# DelayPCB.net
KiCad netlist of a schematic drawn in EasyEDA
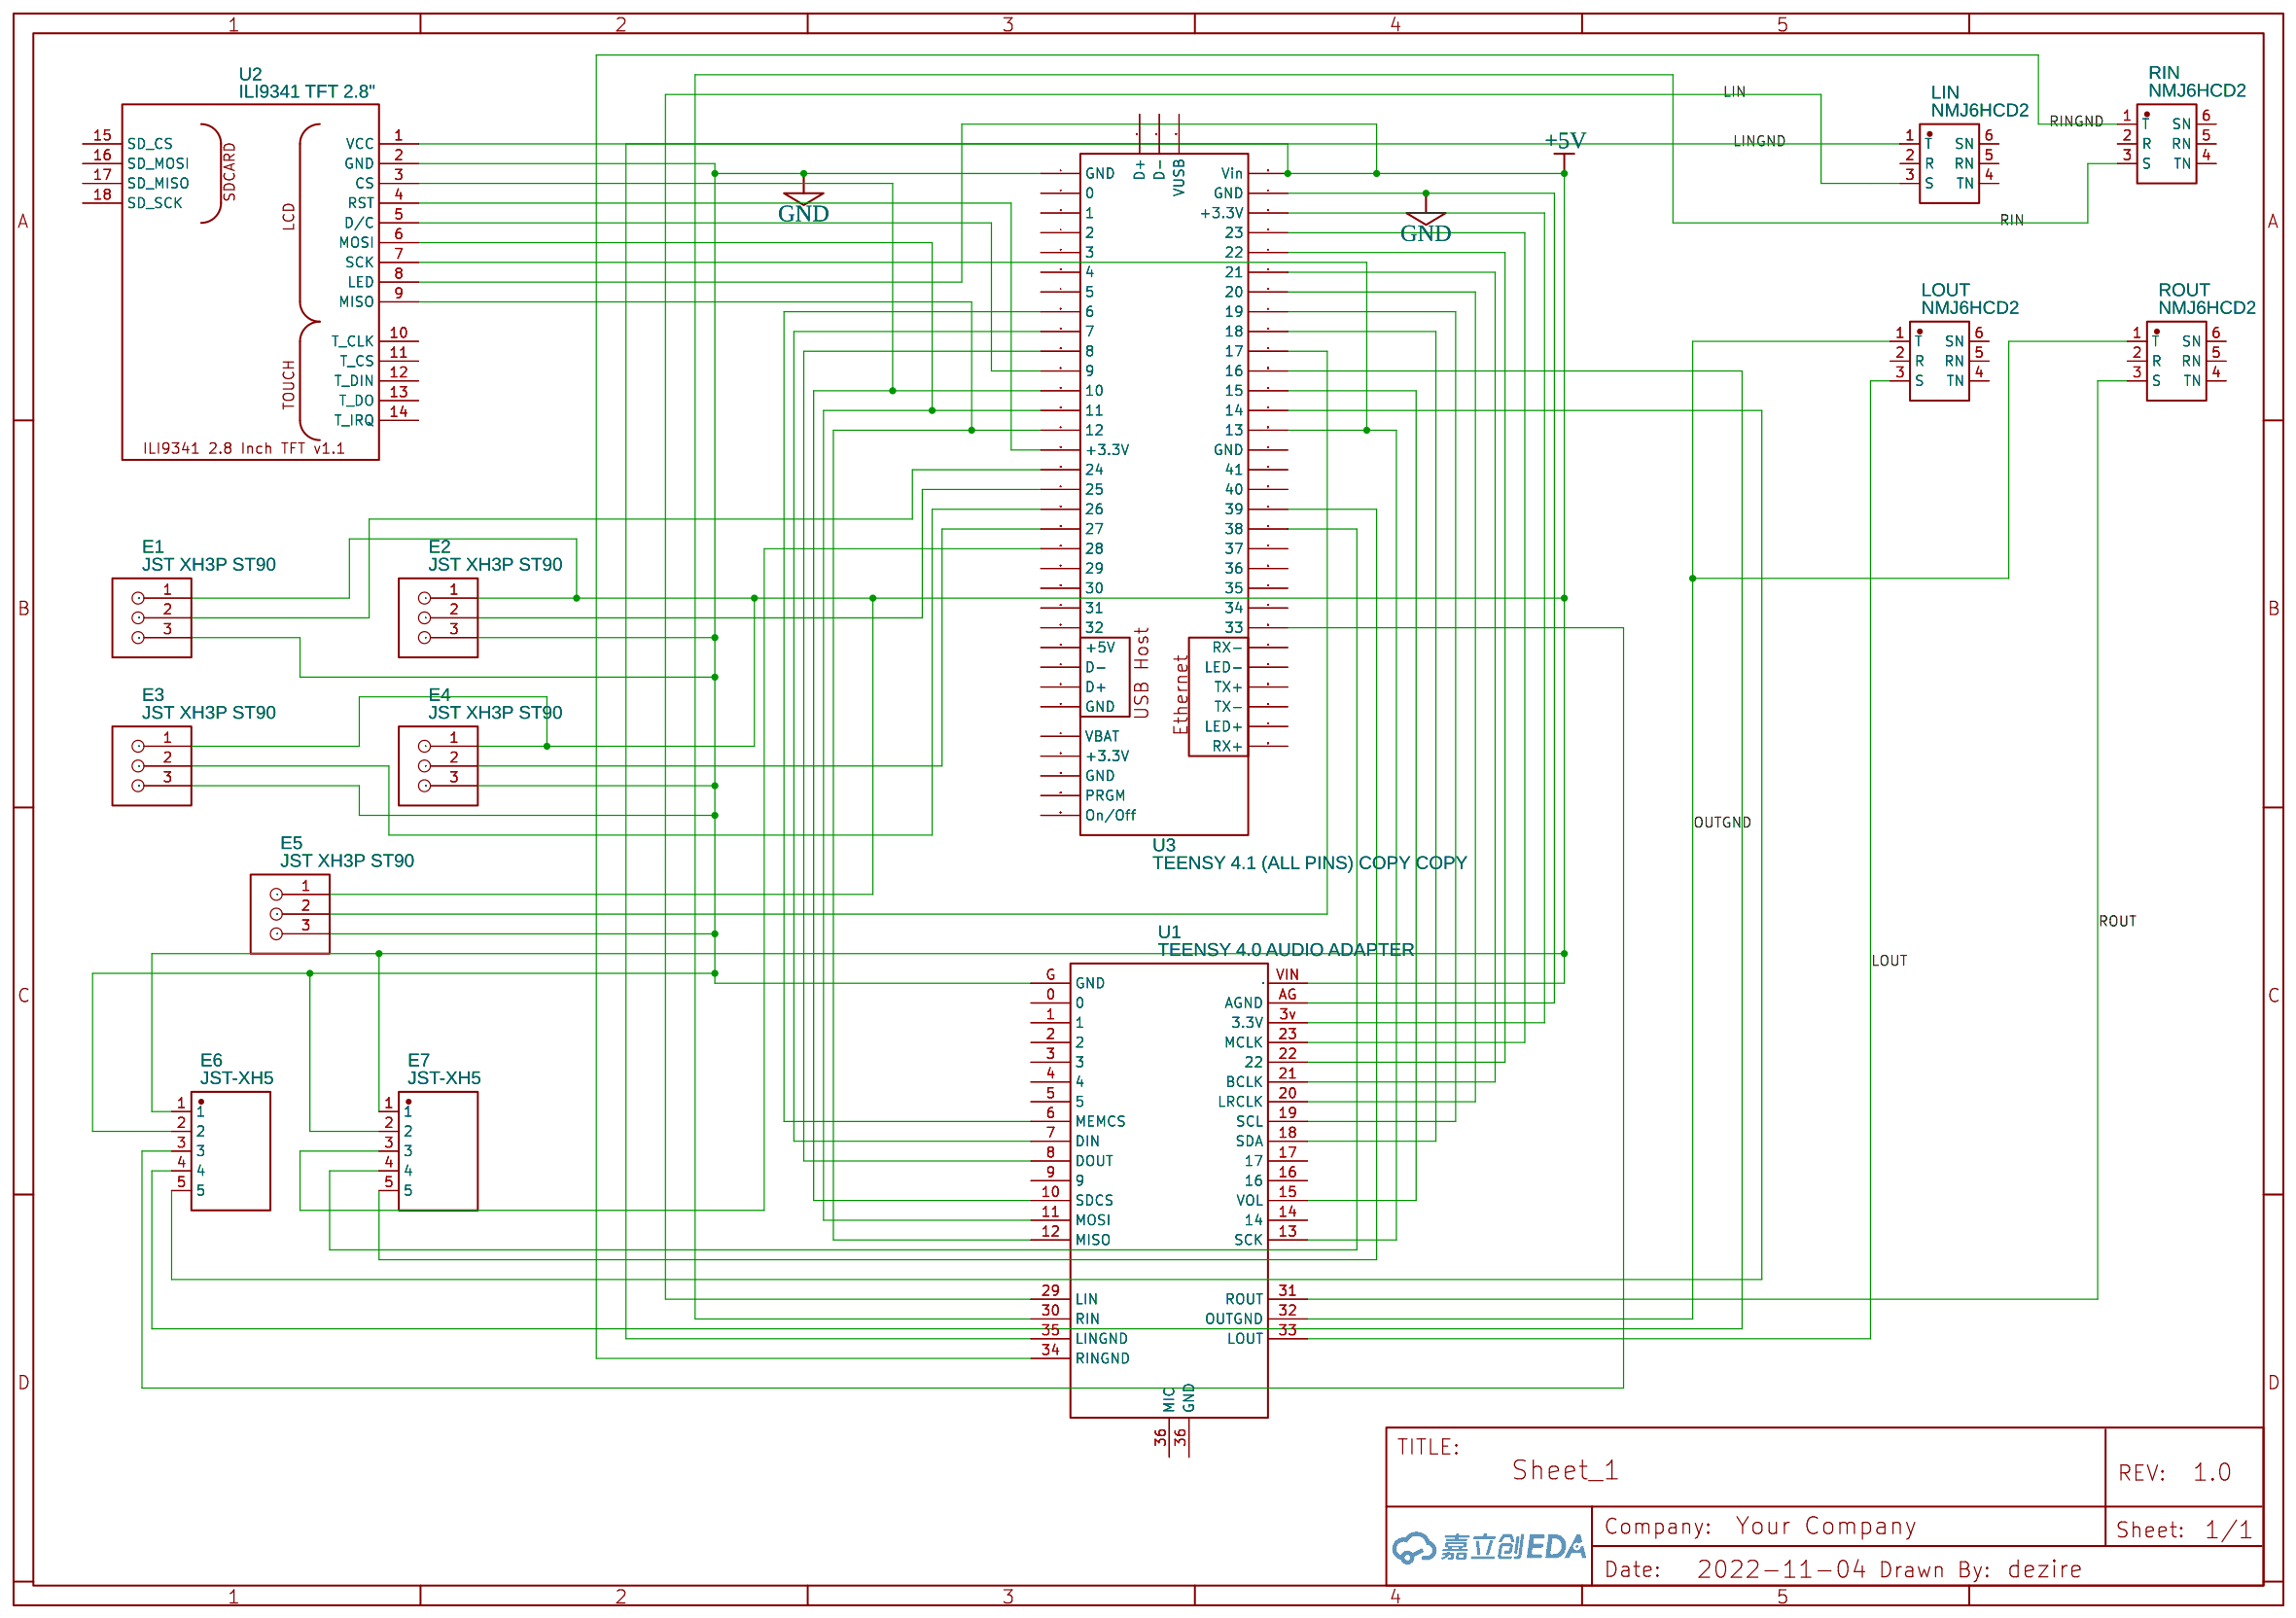
[diagram p0: schematic sheet]

(export (version "E")
  (design (tool "Eeschema 10.0.6"))
  (components
    (comp (ref "E1") (value "JST XH3P ST90") (libsource (lib "") (part "JST XH3P ST90")))
    (comp (ref "E2") (value "JST XH3P ST90") (libsource (lib "") (part "JST XH3P ST90")))
    (comp (ref "E3") (value "JST XH3P ST90") (libsource (lib "") (part "JST XH3P ST90")))
    (comp (ref "E4") (value "JST XH3P ST90") (libsource (lib "") (part "JST XH3P ST90")))
    (comp (ref "E5") (value "JST XH3P ST90") (libsource (lib "") (part "JST XH3P ST90")))
    (comp (ref "E6")
      (value "JST-XH5")
      (fields (field (name "BOM_Supplier Part") "JST XH5P ST"))
      (libsource (lib "") (part "JST-XH5"))
    )
    (comp (ref "E7")
      (value "JST-XH5")
      (fields (field (name "BOM_Supplier Part") "JST XH5P ST"))
      (libsource (lib "") (part "JST-XH5"))
    )
    (comp (ref "LIN")
      (value "NMJ6HCD2")
      (fields (field (name "BOM_Supplier Part") "C368502"))
      (libsource (lib "") (part "NMJ6HCD2_2"))
    )
    (comp (ref "LOUT")
      (value "NMJ6HCD2")
      (fields (field (name "BOM_Supplier Part") "C368502"))
      (libsource (lib "") (part "NMJ6HCD2_3"))
    )
    (comp (ref "RIN")
      (value "NMJ6HCD2")
      (fields (field (name "BOM_Supplier Part") "C368502"))
      (libsource (lib "") (part "NMJ6HCD2_1"))
    )
    (comp (ref "ROUT")
      (value "NMJ6HCD2")
      (fields (field (name "BOM_Supplier Part") "C368502"))
      (libsource (lib "") (part "NMJ6HCD2"))
    )
    (comp (ref "U1")
      (value "TEENSY 4.0 AUDIO ADAPTER")
      (fields (field (name "BOM_Manufacturer Part") "New SchematicLib"))
      (libsource (lib "") (part "TEENSY 4.0 AUDIO ADAPTER"))
    )
    (comp (ref "U2") (value "ILI9341 TFT 2.8\"") (libsource (lib "") (part "ILI9341 TFT 2.8{dblquote}")))
    (comp (ref "U3")
      (value "TEENSY 4.1 (ALL PINS) COPY COPY")
      (libsource (lib "") (part "TEENSY 4.1 (ALL PINS) COPY COPY"))
    )
  )
  (nets
    (net (code "1") (name "+5V") (class "Default")
      (node (ref "E1") (pin "1") (pinfunction "1_1") (pintype "bidirectional"))
      (node (ref "E2") (pin "1") (pinfunction "1_1") (pintype "bidirectional"))
      (node (ref "E3") (pin "1") (pinfunction "1_1") (pintype "bidirectional"))
      (node (ref "E4") (pin "1") (pinfunction "1_1") (pintype "bidirectional"))
      (node (ref "E5") (pin "1") (pinfunction "1_1") (pintype "bidirectional"))
      (node (ref "E6") (pin "1") (pinfunction "1_1") (pintype "unspecified"))
      (node (ref "E7") (pin "1") (pinfunction "1_1") (pintype "unspecified"))
      (node (ref "U1") (pin "VIN") (pinfunction "28_VIN") (pintype "unspecified"))
      (node (ref "U2") (pin "1") (pinfunction "VCC_1") (pintype "unspecified"))
      (node (ref "U2") (pin "8") (pinfunction "LED_8") (pintype "unspecified"))
      (node (ref "U3") (pin "48") (pinfunction "Vin_48") (pintype "unspecified"))
    )
    (net (code "2") (name "/LIN") (class "Default")
      (node (ref "LIN") (pin "3") (pinfunction "S_3") (pintype "unspecified"))
      (node (ref "U1") (pin "29") (pinfunction "LIN_29") (pintype "unspecified"))
    )
    (net (code "3") (name "/LINGND") (class "Default")
      (node (ref "LIN") (pin "1") (pinfunction "T_1") (pintype "unspecified"))
      (node (ref "U1") (pin "35") (pinfunction "LINGND_35") (pintype "unspecified"))
    )
    (net (code "4") (name "/LOUT") (class "Default")
      (node (ref "LOUT") (pin "3") (pinfunction "S_3") (pintype "unspecified"))
      (node (ref "U1") (pin "33") (pinfunction "LOUT_33") (pintype "unspecified"))
    )
    (net (code "5") (name "/OUTGND") (class "Default")
      (node (ref "LOUT") (pin "1") (pinfunction "T_1") (pintype "unspecified"))
      (node (ref "ROUT") (pin "1") (pinfunction "T_1") (pintype "unspecified"))
      (node (ref "U1") (pin "32") (pinfunction "OUTGND_32") (pintype "unspecified"))
    )
    (net (code "6") (name "/RIN") (class "Default")
      (node (ref "RIN") (pin "3") (pinfunction "S_3") (pintype "unspecified"))
      (node (ref "U1") (pin "30") (pinfunction "RIN_30") (pintype "unspecified"))
    )
    (net (code "7") (name "/RINGND") (class "Default")
      (node (ref "RIN") (pin "1") (pinfunction "T_1") (pintype "unspecified"))
      (node (ref "U1") (pin "34") (pinfunction "RINGND_34") (pintype "unspecified"))
    )
    (net (code "8") (name "/ROUT") (class "Default")
      (node (ref "ROUT") (pin "3") (pinfunction "S_3") (pintype "unspecified"))
      (node (ref "U1") (pin "31") (pinfunction "ROUT_31") (pintype "unspecified"))
    )
    (net (code "9") (name "GND") (class "Default")
      (node (ref "E1") (pin "3") (pinfunction "3_3") (pintype "bidirectional"))
      (node (ref "E2") (pin "3") (pinfunction "3_3") (pintype "bidirectional"))
      (node (ref "E3") (pin "3") (pinfunction "3_3") (pintype "bidirectional"))
      (node (ref "E4") (pin "3") (pinfunction "3_3") (pintype "bidirectional"))
      (node (ref "E5") (pin "3") (pinfunction "3_3") (pintype "bidirectional"))
      (node (ref "E6") (pin "2") (pinfunction "2_2") (pintype "unspecified"))
      (node (ref "E7") (pin "2") (pinfunction "2_2") (pintype "unspecified"))
      (node (ref "U1") (pin "AG") (pinfunction "AGND_AG") (pintype "unspecified"))
      (node (ref "U1") (pin "G") (pinfunction "GND_G") (pintype "unspecified"))
      (node (ref "U2") (pin "2") (pinfunction "GND_2") (pintype "unspecified"))
      (node (ref "U3") (pin "1") (pinfunction "GND_1") (pintype "unspecified"))
      (node (ref "U3") (pin "47") (pinfunction "GND_47") (pintype "unspecified"))
    )
    (net (code "10") (name "Net-(U1-3.3V)") (class "Default")
      (node (ref "U1") (pin "3v") (pinfunction "3.3V_3v") (pintype "unspecified"))
      (node (ref "U3") (pin "46") (pinfunction "+3.3V_46") (pintype "unspecified"))
    )
    (net (code "11") (name "Net-(U1-BCLK)") (class "Default")
      (node (ref "U1") (pin "21") (pinfunction "BCLK_21") (pintype "unspecified"))
      (node (ref "U3") (pin "43") (pinfunction "21_43") (pintype "unspecified"))
    )
    (net (code "12") (name "Net-(U1-DIN)") (class "Default")
      (node (ref "U1") (pin "7") (pinfunction "DIN_7") (pintype "unspecified"))
      (node (ref "U3") (pin "9") (pinfunction "7_9") (pintype "unspecified"))
    )
    (net (code "13") (name "Net-(U1-DOUT)") (class "Default")
      (node (ref "U1") (pin "8") (pinfunction "DOUT_8") (pintype "unspecified"))
      (node (ref "U3") (pin "10") (pinfunction "8_10") (pintype "unspecified"))
    )
    (net (code "14") (name "Net-(U1-LRCLK)") (class "Default")
      (node (ref "U1") (pin "20") (pinfunction "LRCLK_20") (pintype "unspecified"))
      (node (ref "U3") (pin "42") (pinfunction "20_42") (pintype "unspecified"))
    )
    (net (code "15") (name "Net-(U1-MCLK)") (class "Default")
      (node (ref "U1") (pin "23") (pinfunction "MCLK_23") (pintype "unspecified"))
      (node (ref "U3") (pin "45") (pinfunction "23_45") (pintype "unspecified"))
    )
    (net (code "16") (name "Net-(U1-MEMCS)") (class "Default")
      (node (ref "U1") (pin "6") (pinfunction "MEMCS_6") (pintype "unspecified"))
      (node (ref "U3") (pin "8") (pinfunction "6_8") (pintype "unspecified"))
    )
    (net (code "17") (name "Net-(U1-MISO)") (class "Default")
      (node (ref "U1") (pin "12") (pinfunction "MISO_12") (pintype "unspecified"))
      (node (ref "U2") (pin "9") (pinfunction "MISO_9") (pintype "unspecified"))
      (node (ref "U3") (pin "14") (pinfunction "12_14") (pintype "unspecified"))
    )
    (net (code "18") (name "Net-(U1-MOSI)") (class "Default")
      (node (ref "U1") (pin "11") (pinfunction "MOSI_11") (pintype "unspecified"))
      (node (ref "U2") (pin "6") (pinfunction "MOSI_6") (pintype "unspecified"))
      (node (ref "U3") (pin "13") (pinfunction "11_13") (pintype "unspecified"))
    )
    (net (code "19") (name "Net-(U1-SCK)") (class "Default")
      (node (ref "U1") (pin "13") (pinfunction "SCK_13") (pintype "unspecified"))
      (node (ref "U2") (pin "7") (pinfunction "SCK_7") (pintype "unspecified"))
      (node (ref "U3") (pin "35") (pinfunction "13_35") (pintype "unspecified"))
    )
    (net (code "20") (name "Net-(U1-SCL)") (class "Default")
      (node (ref "U1") (pin "19") (pinfunction "SCL_19") (pintype "unspecified"))
      (node (ref "U3") (pin "41") (pinfunction "19_41") (pintype "unspecified"))
    )
    (net (code "21") (name "Net-(U1-SDA)") (class "Default")
      (node (ref "U1") (pin "18") (pinfunction "SDA_18") (pintype "unspecified"))
      (node (ref "U3") (pin "40") (pinfunction "18_40") (pintype "unspecified"))
    )
    (net (code "22") (name "Net-(U1-SDCS)") (class "Default")
      (node (ref "U1") (pin "10") (pinfunction "SDCS_10") (pintype "unspecified"))
      (node (ref "U2") (pin "3") (pinfunction "CS_3") (pintype "unspecified"))
      (node (ref "U3") (pin "12") (pinfunction "10_12") (pintype "unspecified"))
    )
    (net (code "23") (name "Net-(U1-VOL)") (class "Default")
      (node (ref "U1") (pin "15") (pinfunction "VOL_15") (pintype "unspecified"))
      (node (ref "U3") (pin "37") (pinfunction "15_37") (pintype "unspecified"))
    )
    (net (code "24") (name "Net-(U2-D{slash}C)") (class "Default")
      (node (ref "U2") (pin "5") (pinfunction "D/C_5") (pintype "unspecified"))
      (node (ref "U3") (pin "11") (pinfunction "9_11") (pintype "unspecified"))
    )
    (net (code "25") (name "Net-(U2-RST)") (class "Default")
      (node (ref "U2") (pin "4") (pinfunction "RST_4") (pintype "unspecified"))
      (node (ref "U3") (pin "15") (pinfunction "+3.3V_15") (pintype "unspecified"))
    )
    (net (code "26") (name "Net-(U3-14)") (class "Default")
      (node (ref "E6") (pin "5") (pinfunction "5_5") (pintype "unspecified"))
      (node (ref "U3") (pin "36") (pinfunction "14_36") (pintype "unspecified"))
    )
    (net (code "27") (name "Net-(U3-16)") (class "Default")
      (node (ref "E6") (pin "4") (pinfunction "4_4") (pintype "unspecified"))
      (node (ref "U3") (pin "38") (pinfunction "16_38") (pintype "unspecified"))
    )
    (net (code "28") (name "Net-(U3-17)") (class "Default")
      (node (ref "E5") (pin "2") (pinfunction "2_2") (pintype "bidirectional"))
      (node (ref "U3") (pin "39") (pinfunction "17_39") (pintype "unspecified"))
    )
    (net (code "29") (name "Net-(U3-22)") (class "Default")
      (node (ref "U1") (pin "22") (pinfunction "22_22") (pintype "unspecified"))
      (node (ref "U3") (pin "44") (pinfunction "22_44") (pintype "unspecified"))
    )
    (net (code "30") (name "Net-(U3-24)") (class "Default")
      (node (ref "E1") (pin "2") (pinfunction "2_2") (pintype "bidirectional"))
      (node (ref "U3") (pin "16") (pinfunction "24_16") (pintype "unspecified"))
    )
    (net (code "31") (name "Net-(U3-25)") (class "Default")
      (node (ref "E2") (pin "2") (pinfunction "2_2") (pintype "bidirectional"))
      (node (ref "U3") (pin "17") (pinfunction "25_17") (pintype "unspecified"))
    )
    (net (code "32") (name "Net-(U3-26)") (class "Default")
      (node (ref "E3") (pin "2") (pinfunction "2_2") (pintype "bidirectional"))
      (node (ref "U3") (pin "18") (pinfunction "26_18") (pintype "unspecified"))
    )
    (net (code "33") (name "Net-(U3-27)") (class "Default")
      (node (ref "E4") (pin "2") (pinfunction "2_2") (pintype "bidirectional"))
      (node (ref "U3") (pin "19") (pinfunction "27_19") (pintype "unspecified"))
    )
    (net (code "34") (name "Net-(U3-28)") (class "Default")
      (node (ref "E7") (pin "3") (pinfunction "3_3") (pintype "unspecified"))
      (node (ref "U3") (pin "20") (pinfunction "28_20") (pintype "unspecified"))
    )
    (net (code "35") (name "Net-(U3-33)") (class "Default")
      (node (ref "E6") (pin "3") (pinfunction "3_3") (pintype "unspecified"))
      (node (ref "U3") (pin "25") (pinfunction "33_25") (pintype "unspecified"))
    )
    (net (code "36") (name "Net-(U3-38)") (class "Default")
      (node (ref "E7") (pin "4") (pinfunction "4_4") (pintype "unspecified"))
      (node (ref "U3") (pin "30") (pinfunction "38_30") (pintype "unspecified"))
    )
    (net (code "37") (name "Net-(U3-39)") (class "Default")
      (node (ref "E7") (pin "5") (pinfunction "5_5") (pintype "unspecified"))
      (node (ref "U3") (pin "31") (pinfunction "39_31") (pintype "unspecified"))
    )
    (net (code "38") (name "unconnected-(LIN-R-Pad2)") (class "Default")
      (node (ref "LIN") (pin "2") (pinfunction "R_2") (pintype "unspecified"))
    )
    (net (code "39") (name "unconnected-(LIN-RN-Pad5)") (class "Default")
      (node (ref "LIN") (pin "5") (pinfunction "RN_5") (pintype "unspecified"))
    )
    (net (code "40") (name "unconnected-(LIN-SN-Pad6)") (class "Default")
      (node (ref "LIN") (pin "6") (pinfunction "SN_6") (pintype "unspecified"))
    )
    (net (code "41") (name "unconnected-(LIN-TN-Pad4)") (class "Default")
      (node (ref "LIN") (pin "4") (pinfunction "TN_4") (pintype "unspecified"))
    )
    (net (code "42") (name "unconnected-(LOUT-R-Pad2)") (class "Default")
      (node (ref "LOUT") (pin "2") (pinfunction "R_2") (pintype "unspecified"))
    )
    (net (code "43") (name "unconnected-(LOUT-RN-Pad5)") (class "Default")
      (node (ref "LOUT") (pin "5") (pinfunction "RN_5") (pintype "unspecified"))
    )
    (net (code "44") (name "unconnected-(LOUT-SN-Pad6)") (class "Default")
      (node (ref "LOUT") (pin "6") (pinfunction "SN_6") (pintype "unspecified"))
    )
    (net (code "45") (name "unconnected-(LOUT-TN-Pad4)") (class "Default")
      (node (ref "LOUT") (pin "4") (pinfunction "TN_4") (pintype "unspecified"))
    )
    (net (code "46") (name "unconnected-(RIN-R-Pad2)") (class "Default")
      (node (ref "RIN") (pin "2") (pinfunction "R_2") (pintype "unspecified"))
    )
    (net (code "47") (name "unconnected-(RIN-RN-Pad5)") (class "Default")
      (node (ref "RIN") (pin "5") (pinfunction "RN_5") (pintype "unspecified"))
    )
    (net (code "48") (name "unconnected-(RIN-SN-Pad6)") (class "Default")
      (node (ref "RIN") (pin "6") (pinfunction "SN_6") (pintype "unspecified"))
    )
    (net (code "49") (name "unconnected-(RIN-TN-Pad4)") (class "Default")
      (node (ref "RIN") (pin "4") (pinfunction "TN_4") (pintype "unspecified"))
    )
    (net (code "50") (name "unconnected-(ROUT-R-Pad2)") (class "Default")
      (node (ref "ROUT") (pin "2") (pinfunction "R_2") (pintype "unspecified"))
    )
    (net (code "51") (name "unconnected-(ROUT-RN-Pad5)") (class "Default")
      (node (ref "ROUT") (pin "5") (pinfunction "RN_5") (pintype "unspecified"))
    )
    (net (code "52") (name "unconnected-(ROUT-SN-Pad6)") (class "Default")
      (node (ref "ROUT") (pin "6") (pinfunction "SN_6") (pintype "unspecified"))
    )
    (net (code "53") (name "unconnected-(ROUT-TN-Pad4)") (class "Default")
      (node (ref "ROUT") (pin "4") (pinfunction "TN_4") (pintype "unspecified"))
    )
    (net (code "54") (name "unconnected-(U1-GND-Pad36)") (class "Default")
      (node (ref "U1") (pin "36") (pinfunction "GND_36") (pintype "unspecified"))
    )
    (net (code "55") (name "unconnected-(U1-MIC-Pad36)") (class "Default")
      (node (ref "U1") (pin "36") (pinfunction "MIC_36") (pintype "unspecified"))
    )
    (net (code "56") (name "unconnected-(U1-Pad0)") (class "Default")
      (node (ref "U1") (pin "0") (pinfunction "0_0") (pintype "unspecified"))
    )
    (net (code "57") (name "unconnected-(U1-Pad1)") (class "Default")
      (node (ref "U1") (pin "1") (pinfunction "1_1") (pintype "unspecified"))
    )
    (net (code "58") (name "unconnected-(U1-Pad2)") (class "Default")
      (node (ref "U1") (pin "2") (pinfunction "2_2") (pintype "unspecified"))
    )
    (net (code "59") (name "unconnected-(U1-Pad3)") (class "Default")
      (node (ref "U1") (pin "3") (pinfunction "3_3") (pintype "unspecified"))
    )
    (net (code "60") (name "unconnected-(U1-Pad4)") (class "Default")
      (node (ref "U1") (pin "4") (pinfunction "4_4") (pintype "unspecified"))
    )
    (net (code "61") (name "unconnected-(U1-Pad5)") (class "Default")
      (node (ref "U1") (pin "5") (pinfunction "5_5") (pintype "unspecified"))
    )
    (net (code "62") (name "unconnected-(U1-Pad9)") (class "Default")
      (node (ref "U1") (pin "9") (pinfunction "9_9") (pintype "unspecified"))
    )
    (net (code "63") (name "unconnected-(U1-Pad14)") (class "Default")
      (node (ref "U1") (pin "14") (pinfunction "14_14") (pintype "unspecified"))
    )
    (net (code "64") (name "unconnected-(U1-Pad16)") (class "Default")
      (node (ref "U1") (pin "16") (pinfunction "16_16") (pintype "unspecified"))
    )
    (net (code "65") (name "unconnected-(U1-Pad17)") (class "Default")
      (node (ref "U1") (pin "17") (pinfunction "17_17") (pintype "unspecified"))
    )
    (net (code "66") (name "unconnected-(U2-SD_CS-Pad15)") (class "Default")
      (node (ref "U2") (pin "15") (pinfunction "SD_CS_15") (pintype "unspecified"))
    )
    (net (code "67") (name "unconnected-(U2-SD_MISO-Pad17)") (class "Default")
      (node (ref "U2") (pin "17") (pinfunction "SD_MISO_17") (pintype "unspecified"))
    )
    (net (code "68") (name "unconnected-(U2-SD_MOSI-Pad16)") (class "Default")
      (node (ref "U2") (pin "16") (pinfunction "SD_MOSI_16") (pintype "unspecified"))
    )
    (net (code "69") (name "unconnected-(U2-SD_SCK-Pad18)") (class "Default")
      (node (ref "U2") (pin "18") (pinfunction "SD_SCK_18") (pintype "unspecified"))
    )
    (net (code "70") (name "unconnected-(U2-T_CLK-Pad10)") (class "Default")
      (node (ref "U2") (pin "10") (pinfunction "T_CLK_10") (pintype "unspecified"))
    )
    (net (code "71") (name "unconnected-(U2-T_CS-Pad11)") (class "Default")
      (node (ref "U2") (pin "11") (pinfunction "T_CS_11") (pintype "unspecified"))
    )
    (net (code "72") (name "unconnected-(U2-T_DIN-Pad12)") (class "Default")
      (node (ref "U2") (pin "12") (pinfunction "T_DIN_12") (pintype "unspecified"))
    )
    (net (code "73") (name "unconnected-(U2-T_DO-Pad13)") (class "Default")
      (node (ref "U2") (pin "13") (pinfunction "T_DO_13") (pintype "unspecified"))
    )
    (net (code "74") (name "unconnected-(U2-T_IRQ-Pad14)") (class "Default")
      (node (ref "U2") (pin "14") (pinfunction "T_IRQ_14") (pintype "unspecified"))
    )
    (net (code "75") (name "unconnected-(U3-+3.3V-Pad48)") (class "Default")
      (node (ref "U3") (pin "48") (pinfunction "+3.3V_48") (pintype "unspecified"))
    )
    (net (code "76") (name "unconnected-(U3-+5V-Pad45)") (class "Default")
      (node (ref "U3") (pin "45") (pinfunction "+5V_45") (pintype "unspecified"))
    )
    (net (code "77") (name "unconnected-(U3-0-Pad2)") (class "Default")
      (node (ref "U3") (pin "2") (pinfunction "0_2") (pintype "unspecified"))
    )
    (net (code "78") (name "unconnected-(U3-1-Pad3)") (class "Default")
      (node (ref "U3") (pin "3") (pinfunction "1_3") (pintype "unspecified"))
    )
    (net (code "79") (name "unconnected-(U3-2-Pad4)") (class "Default")
      (node (ref "U3") (pin "4") (pinfunction "2_4") (pintype "unspecified"))
    )
    (net (code "80") (name "unconnected-(U3-3-Pad5)") (class "Default")
      (node (ref "U3") (pin "5") (pinfunction "3_5") (pintype "unspecified"))
    )
    (net (code "81") (name "unconnected-(U3-4-Pad6)") (class "Default")
      (node (ref "U3") (pin "6") (pinfunction "4_6") (pintype "unspecified"))
    )
    (net (code "82") (name "unconnected-(U3-5-Pad7)") (class "Default")
      (node (ref "U3") (pin "7") (pinfunction "5_7") (pintype "unspecified"))
    )
    (net (code "83") (name "unconnected-(U3-29-Pad21)") (class "Default")
      (node (ref "U3") (pin "21") (pinfunction "29_21") (pintype "unspecified"))
    )
    (net (code "84") (name "unconnected-(U3-30-Pad22)") (class "Default")
      (node (ref "U3") (pin "22") (pinfunction "30_22") (pintype "unspecified"))
    )
    (net (code "85") (name "unconnected-(U3-31-Pad23)") (class "Default")
      (node (ref "U3") (pin "23") (pinfunction "31_23") (pintype "unspecified"))
    )
    (net (code "86") (name "unconnected-(U3-32-Pad24)") (class "Default")
      (node (ref "U3") (pin "24") (pinfunction "32_24") (pintype "unspecified"))
    )
    (net (code "87") (name "unconnected-(U3-34-Pad26)") (class "Default")
      (node (ref "U3") (pin "26") (pinfunction "34_26") (pintype "unspecified"))
    )
    (net (code "88") (name "unconnected-(U3-35-Pad27)") (class "Default")
      (node (ref "U3") (pin "27") (pinfunction "35_27") (pintype "unspecified"))
    )
    (net (code "89") (name "unconnected-(U3-36-Pad28)") (class "Default")
      (node (ref "U3") (pin "28") (pinfunction "36_28") (pintype "unspecified"))
    )
    (net (code "90") (name "unconnected-(U3-37-Pad29)") (class "Default")
      (node (ref "U3") (pin "29") (pinfunction "37_29") (pintype "unspecified"))
    )
    (net (code "91") (name "unconnected-(U3-40-Pad32)") (class "Default")
      (node (ref "U3") (pin "32") (pinfunction "40_32") (pintype "unspecified"))
    )
    (net (code "92") (name "unconnected-(U3-41-Pad33)") (class "Default")
      (node (ref "U3") (pin "33") (pinfunction "41_33") (pintype "unspecified"))
    )
    (net (code "93") (name "unconnected-(U3-D+-Pad43)") (class "Default")
      (node (ref "U3") (pin "43") (pinfunction "D+_43") (pintype "unspecified"))
    )
    (net (code "94") (name "unconnected-(U3-D+-Pad66)") (class "Default")
      (node (ref "U3") (pin "66") (pinfunction "D+_66") (pintype "unspecified"))
    )
    (net (code "95") (name "unconnected-(U3-D--Pad44)") (class "Default")
      (node (ref "U3") (pin "44") (pinfunction "D-_44") (pintype "unspecified"))
    )
    (net (code "96") (name "unconnected-(U3-D--Pad67)") (class "Default")
      (node (ref "U3") (pin "67") (pinfunction "D-_67") (pintype "unspecified"))
    )
    (net (code "97") (name "unconnected-(U3-GND-Pad34)") (class "Default")
      (node (ref "U3") (pin "34") (pinfunction "GND_34") (pintype "unspecified"))
    )
    (net (code "98") (name "unconnected-(U3-GND-Pad42)") (class "Default")
      (node (ref "U3") (pin "42") (pinfunction "GND_42") (pintype "unspecified"))
    )
    (net (code "99") (name "unconnected-(U3-GND-Pad49)") (class "Default")
      (node (ref "U3") (pin "49") (pinfunction "GND_49") (pintype "unspecified"))
    )
    (net (code "100") (name "unconnected-(U3-LED+-Pad61)") (class "Default")
      (node (ref "U3") (pin "61") (pinfunction "LED+_61") (pintype "unspecified"))
    )
    (net (code "101") (name "unconnected-(U3-LED--Pad64)") (class "Default")
      (node (ref "U3") (pin "64") (pinfunction "LED-_64") (pintype "unspecified"))
    )
    (net (code "102") (name "unconnected-(U3-On{slash}Off-Pad51)") (class "Default")
      (node (ref "U3") (pin "51") (pinfunction "On/Off_51") (pintype "unspecified"))
    )
    (net (code "103") (name "unconnected-(U3-PRGM-Pad50)") (class "Default")
      (node (ref "U3") (pin "50") (pinfunction "PRGM_50") (pintype "unspecified"))
    )
    (net (code "104") (name "unconnected-(U3-RX+-Pad60)") (class "Default")
      (node (ref "U3") (pin "60") (pinfunction "RX+_60") (pintype "unspecified"))
    )
    (net (code "105") (name "unconnected-(U3-RX--Pad65)") (class "Default")
      (node (ref "U3") (pin "65") (pinfunction "RX-_65") (pintype "unspecified"))
    )
    (net (code "106") (name "unconnected-(U3-TX+-Pad63)") (class "Default")
      (node (ref "U3") (pin "63") (pinfunction "TX+_63") (pintype "unspecified"))
    )
    (net (code "107") (name "unconnected-(U3-TX--Pad62)") (class "Default")
      (node (ref "U3") (pin "62") (pinfunction "TX-_62") (pintype "unspecified"))
    )
    (net (code "108") (name "unconnected-(U3-VBAT-Pad47)") (class "Default")
      (node (ref "U3") (pin "47") (pinfunction "VBAT_47") (pintype "unspecified"))
    )
    (net (code "109") (name "unconnected-(U3-VUSB-Pad52)") (class "Default")
      (node (ref "U3") (pin "52") (pinfunction "VUSB_52") (pintype "unspecified"))
    )
  )
)
